# ANET3D_LCD12864_Board.net
KiCad netlist of a schematic drawn in EAGLE
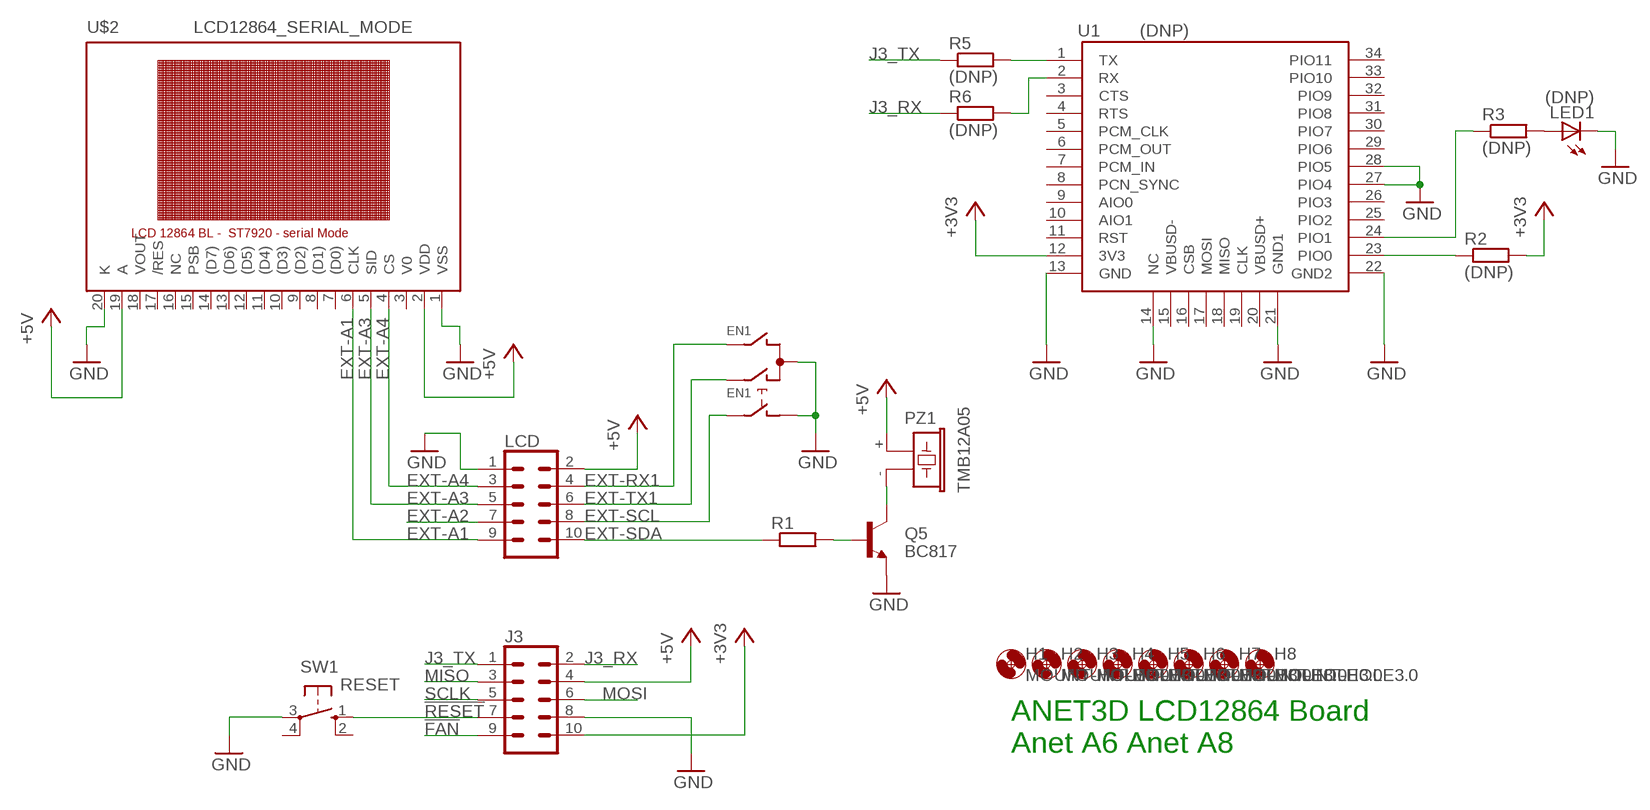
[diagram p0: schematic, sheet 1]

(export (version "E")
  (design (tool "Eeschema 10.0.6"))
  (components
    (comp (ref "EN1")
      (value "EC12E_SW")
      (footprint "eagle-import:ALPS_EC12E_SW")
      (fields (field (name "MPN") "EC12E2424407"))
      (libsource (lib "eagle-import") (part "EC12E_SW"))
    )
    (comp (ref "H1")
      (value "MOUNT-HOLE3.0")
      (footprint "eagle-import:3,0")
      (libsource (lib "eagle-import") (part "MOUNT-HOLE3.0"))
    )
    (comp (ref "H2")
      (value "MOUNT-HOLE3.0")
      (footprint "eagle-import:3,0")
      (libsource (lib "eagle-import") (part "MOUNT-HOLE3.0"))
    )
    (comp (ref "H3")
      (value "MOUNT-HOLE3.0")
      (footprint "eagle-import:3,0")
      (libsource (lib "eagle-import") (part "MOUNT-HOLE3.0"))
    )
    (comp (ref "H4")
      (value "MOUNT-HOLE3.0")
      (footprint "eagle-import:3,0")
      (libsource (lib "eagle-import") (part "MOUNT-HOLE3.0"))
    )
    (comp (ref "H5")
      (value "MOUNT-HOLE3.0")
      (footprint "eagle-import:3,0")
      (libsource (lib "eagle-import") (part "MOUNT-HOLE3.0"))
    )
    (comp (ref "H6")
      (value "MOUNT-HOLE3.0")
      (footprint "eagle-import:3,0")
      (libsource (lib "eagle-import") (part "MOUNT-HOLE3.0"))
    )
    (comp (ref "H7")
      (value "MOUNT-HOLE3.0")
      (footprint "eagle-import:3,0")
      (libsource (lib "eagle-import") (part "MOUNT-HOLE3.0"))
    )
    (comp (ref "H8")
      (value "MOUNT-HOLE3.0")
      (footprint "eagle-import:3,0")
      (libsource (lib "eagle-import") (part "MOUNT-HOLE3.0"))
    )
    (comp (ref "J3")
      (value "CONN_05X2SHD_SMD")
      (footprint "eagle-import:2X5-SHROUDED_SMD")
      (libsource (lib "eagle-import") (part "CONN_05X2SHD_SMD"))
    )
    (comp (ref "LCD")
      (value "CONN_05X2SHD_SMD")
      (footprint "eagle-import:2X5-SHROUDED_SMD")
      (libsource (lib "eagle-import") (part "CONN_05X2SHD_SMD"))
    )
    (comp (ref "LED1")
      (value "(DNP)")
      (footprint "eagle-import:CHIPLED_0805")
      (libsource (lib "eagle-import") (part "LEDCHIPLED_0805"))
    )
    (comp (ref "PZ1")
      (value "TMB12A05")
      (footprint "eagle-import:F_CM12P")
      (libsource (lib "eagle-import") (part "F/CM12P"))
    )
    (comp (ref "Q5")
      (value "BC817")
      (footprint "eagle-import:SOT23-BEC")
      (libsource (lib "eagle-import") (part "BC817SMD-40LT1"))
    )
    (comp (ref "R1")
      (value "R-EU_R0805")
      (footprint "eagle-import:R0805")
      (libsource (lib "eagle-import") (part "R-EU_R0805"))
    )
    (comp (ref "R2")
      (value "(DNP)")
      (footprint "eagle-import:R0805")
      (libsource (lib "eagle-import") (part "R-EU_R0805"))
    )
    (comp (ref "R3")
      (value "(DNP)")
      (footprint "eagle-import:R0805")
      (libsource (lib "eagle-import") (part "R-EU_R0805"))
    )
    (comp (ref "R5")
      (value "(DNP)")
      (footprint "eagle-import:R0805")
      (libsource (lib "eagle-import") (part "R-EU_R0805"))
    )
    (comp (ref "R6")
      (value "(DNP)")
      (footprint "eagle-import:R0805")
      (libsource (lib "eagle-import") (part "R-EU_R0805"))
    )
    (comp (ref "SW1")
      (value "RESET")
      (footprint "eagle-import:B3F-40XX")
      (fields (field (name "MF") "OMRON COMPONENTS USA") (field (name "MPN") "B3F-4000"))
      (libsource (lib "eagle-import") (part "40-XX"))
    )
    (comp (ref "U$2")
      (value "LCD12864_SERIAL_MODE")
      (footprint "eagle-import:LCD12864")
      (libsource (lib "eagle-import") (part "LCD12864_SERIAL_MODE"))
    )
    (comp (ref "U1")
      (value "(DNP)")
      (footprint "eagle-import:BLUETOOTH_SMD")
      (libsource (lib "eagle-import") (part "HC_05"))
    )
  )
  (nets
    (net (code "1") (name "+3V3") (class "Default")
      (node (ref "J3") (pin "10") (pinfunction "10_10") (pintype "passive"))
      (node (ref "R2") (pin "2") (pinfunction "2_2") (pintype "passive"))
      (node (ref "U1") (pin "12") (pinfunction "3V3_12") (pintype "bidirectional"))
    )
    (net (code "2") (name "+5V") (class "Default")
      (node (ref "J3") (pin "4") (pinfunction "4_4") (pintype "passive"))
      (node (ref "LCD") (pin "2") (pinfunction "2_2") (pintype "passive"))
      (node (ref "PZ1") (pin "+") (pinfunction "1_+") (pintype "passive"))
      (node (ref "U$2") (pin "19") (pinfunction "A_19") (pintype "passive"))
      (node (ref "U$2") (pin "2") (pinfunction "VDD_2") (pintype "power_in"))
    )
    (net (code "3") (name "/EXT-A1") (class "Default")
      (node (ref "LCD") (pin "9") (pinfunction "9_9") (pintype "passive"))
      (node (ref "U$2") (pin "6") (pinfunction "CLK_6") (pintype "input"))
    )
    (net (code "4") (name "/EXT-A2") (class "Default")
      (node (ref "LCD") (pin "7") (pinfunction "7_7") (pintype "passive"))
    )
    (net (code "5") (name "/EXT-A3") (class "Default")
      (node (ref "LCD") (pin "5") (pinfunction "5_5") (pintype "passive"))
      (node (ref "U$2") (pin "5") (pinfunction "SID_5") (pintype "input"))
    )
    (net (code "6") (name "/EXT-A4") (class "Default")
      (node (ref "LCD") (pin "3") (pinfunction "3_3") (pintype "passive"))
      (node (ref "U$2") (pin "4") (pinfunction "CS_4") (pintype "input"))
    )
    (net (code "7") (name "/EXT-RX1") (class "Default")
      (node (ref "EN1") (pin "B") (pinfunction "B_B") (pintype "passive"))
      (node (ref "LCD") (pin "4") (pinfunction "4_4") (pintype "passive"))
    )
    (net (code "8") (name "/EXT-SCL") (class "Default")
      (node (ref "EN1") (pin "E") (pinfunction "2_E") (pintype "passive"))
      (node (ref "LCD") (pin "8") (pinfunction "8_8") (pintype "passive"))
    )
    (net (code "9") (name "/EXT-SDA") (class "Default")
      (node (ref "LCD") (pin "10") (pinfunction "10_10") (pintype "passive"))
      (node (ref "R1") (pin "1") (pinfunction "1_1") (pintype "passive"))
    )
    (net (code "10") (name "/EXT-TX1") (class "Default")
      (node (ref "EN1") (pin "A") (pinfunction "A_A") (pintype "passive"))
      (node (ref "LCD") (pin "6") (pinfunction "6_6") (pintype "passive"))
    )
    (net (code "11") (name "/J3_RX") (class "Default")
      (node (ref "J3") (pin "2") (pinfunction "2_2") (pintype "passive"))
      (node (ref "R6") (pin "1") (pinfunction "1_1") (pintype "passive"))
    )
    (net (code "12") (name "/J3_TX") (class "Default")
      (node (ref "J3") (pin "1") (pinfunction "1_1") (pintype "passive"))
      (node (ref "R5") (pin "1") (pinfunction "1_1") (pintype "passive"))
    )
    (net (code "13") (name "/MISO") (class "Default")
      (node (ref "J3") (pin "3") (pinfunction "3_3") (pintype "passive"))
    )
    (net (code "14") (name "/MOSI") (class "Default")
      (node (ref "J3") (pin "6") (pinfunction "6_6") (pintype "passive"))
    )
    (net (code "15") (name "/SCLK") (class "Default")
      (node (ref "J3") (pin "5") (pinfunction "5_5") (pintype "passive"))
    )
    (net (code "16") (name "/~{FAN}") (class "Default")
      (node (ref "J3") (pin "9") (pinfunction "9_9") (pintype "passive"))
    )
    (net (code "17") (name "/~{RESET}") (class "Default")
      (node (ref "J3") (pin "7") (pinfunction "7_7") (pintype "passive"))
      (node (ref "SW1") (pin "1") (pinfunction "S_1") (pintype "passive"))
    )
    (net (code "18") (name "GND") (class "Default")
      (node (ref "EN1") (pin "C") (pinfunction "C_C") (pintype "passive"))
      (node (ref "EN1") (pin "D") (pinfunction "1_D") (pintype "passive"))
      (node (ref "J3") (pin "8") (pinfunction "8_8") (pintype "passive"))
      (node (ref "LCD") (pin "1") (pinfunction "1_1") (pintype "passive"))
      (node (ref "LED1") (pin "C") (pinfunction "C_C") (pintype "passive"))
      (node (ref "Q5") (pin "E") (pinfunction "E_E") (pintype "passive"))
      (node (ref "SW1") (pin "3") (pinfunction "P_3") (pintype "passive"))
      (node (ref "U$2") (pin "1") (pinfunction "VSS_1") (pintype "power_in"))
      (node (ref "U$2") (pin "20") (pinfunction "K_20") (pintype "passive"))
      (node (ref "U1") (pin "13") (pinfunction "GND_13") (pintype "bidirectional"))
      (node (ref "U1") (pin "14") (pinfunction "NC_14") (pintype "bidirectional"))
      (node (ref "U1") (pin "21") (pinfunction "GND1_21") (pintype "bidirectional"))
      (node (ref "U1") (pin "22") (pinfunction "GND2_22") (pintype "bidirectional"))
      (node (ref "U1") (pin "27") (pinfunction "PIO4_27") (pintype "bidirectional"))
      (node (ref "U1") (pin "28") (pinfunction "PIO5_28") (pintype "bidirectional"))
    )
    (net (code "19") (name "Net-(LED1-PadA)") (class "Default")
      (node (ref "LED1") (pin "A") (pinfunction "A_A") (pintype "passive"))
      (node (ref "R3") (pin "2") (pinfunction "2_2") (pintype "passive"))
    )
    (net (code "20") (name "Net-(PZ1-2)") (class "Default")
      (node (ref "PZ1") (pin "-") (pinfunction "2_-") (pintype "passive"))
      (node (ref "Q5") (pin "C") (pinfunction "C_C") (pintype "passive"))
    )
    (net (code "21") (name "Net-(Q5-PadB)") (class "Default")
      (node (ref "Q5") (pin "B") (pinfunction "B_B") (pintype "passive"))
      (node (ref "R1") (pin "2") (pinfunction "2_2") (pintype "passive"))
    )
    (net (code "22") (name "Net-(U1-PIO0)") (class "Default")
      (node (ref "R2") (pin "1") (pinfunction "1_1") (pintype "passive"))
      (node (ref "U1") (pin "23") (pinfunction "PIO0_23") (pintype "bidirectional"))
    )
    (net (code "23") (name "Net-(U1-PIO1)") (class "Default")
      (node (ref "R3") (pin "1") (pinfunction "1_1") (pintype "passive"))
      (node (ref "U1") (pin "24") (pinfunction "PIO1_24") (pintype "bidirectional"))
    )
    (net (code "24") (name "Net-(U1-RX)") (class "Default")
      (node (ref "R6") (pin "2") (pinfunction "2_2") (pintype "passive"))
      (node (ref "U1") (pin "2") (pinfunction "RX_2") (pintype "bidirectional"))
    )
    (net (code "25") (name "Net-(U1-TX)") (class "Default")
      (node (ref "R5") (pin "2") (pinfunction "2_2") (pintype "passive"))
      (node (ref "U1") (pin "1") (pinfunction "TX_1") (pintype "bidirectional"))
    )
    (net (code "26") (name "unconnected-(SW1-P1-Pad4)") (class "Default")
      (node (ref "SW1") (pin "4") (pinfunction "P1_4") (pintype "passive"))
    )
    (net (code "27") (name "unconnected-(SW1-S1-Pad2)") (class "Default")
      (node (ref "SW1") (pin "2") (pinfunction "S1_2") (pintype "passive"))
    )
    (net (code "28") (name "unconnected-(U$2-(D0)-Pad7)") (class "Default")
      (node (ref "U$2") (pin "7") (pinfunction "(D0)_7") (pintype "bidirectional"))
    )
    (net (code "29") (name "unconnected-(U$2-(D1)-Pad8)") (class "Default")
      (node (ref "U$2") (pin "8") (pinfunction "(D1)_8") (pintype "bidirectional"))
    )
    (net (code "30") (name "unconnected-(U$2-(D2)-Pad9)") (class "Default")
      (node (ref "U$2") (pin "9") (pinfunction "(D2)_9") (pintype "bidirectional"))
    )
    (net (code "31") (name "unconnected-(U$2-(D3)-Pad10)") (class "Default")
      (node (ref "U$2") (pin "10") (pinfunction "(D3)_10") (pintype "bidirectional"))
    )
    (net (code "32") (name "unconnected-(U$2-(D4)-Pad11)") (class "Default")
      (node (ref "U$2") (pin "11") (pinfunction "(D4)_11") (pintype "bidirectional"))
    )
    (net (code "33") (name "unconnected-(U$2-(D5)-Pad12)") (class "Default")
      (node (ref "U$2") (pin "12") (pinfunction "(D5)_12") (pintype "bidirectional"))
    )
    (net (code "34") (name "unconnected-(U$2-(D6)-Pad13)") (class "Default")
      (node (ref "U$2") (pin "13") (pinfunction "(D6)_13") (pintype "bidirectional"))
    )
    (net (code "35") (name "unconnected-(U$2-(D7)-Pad14)") (class "Default")
      (node (ref "U$2") (pin "14") (pinfunction "(D7)_14") (pintype "bidirectional"))
    )
    (net (code "36") (name "unconnected-(U$2-NC-Pad16)") (class "Default")
      (node (ref "U$2") (pin "16") (pinfunction "NC_16") (pintype "input"))
    )
    (net (code "37") (name "unconnected-(U$2-PSB-Pad15)") (class "Default")
      (node (ref "U$2") (pin "15") (pinfunction "PSB_15") (pintype "input"))
    )
    (net (code "38") (name "unconnected-(U$2-V0-Pad3)") (class "Default")
      (node (ref "U$2") (pin "3") (pinfunction "V0_3") (pintype "passive"))
    )
    (net (code "39") (name "unconnected-(U$2-VOUT-Pad18)") (class "Default")
      (node (ref "U$2") (pin "18") (pinfunction "VOUT_18") (pintype "output"))
    )
    (net (code "40") (name "unconnected-(U$2-{slash}RES-Pad17)") (class "Default")
      (node (ref "U$2") (pin "17") (pinfunction "/RES_17") (pintype "input"))
    )
    (net (code "41") (name "unconnected-(U1-AIO0-Pad9)") (class "Default")
      (node (ref "U1") (pin "9") (pinfunction "AIO0_9") (pintype "bidirectional"))
    )
    (net (code "42") (name "unconnected-(U1-AIO1-Pad10)") (class "Default")
      (node (ref "U1") (pin "10") (pinfunction "AIO1_10") (pintype "bidirectional"))
    )
    (net (code "43") (name "unconnected-(U1-CLK-Pad19)") (class "Default")
      (node (ref "U1") (pin "19") (pinfunction "CLK_19") (pintype "bidirectional"))
    )
    (net (code "44") (name "unconnected-(U1-CSB-Pad16)") (class "Default")
      (node (ref "U1") (pin "16") (pinfunction "CSB_16") (pintype "bidirectional"))
    )
    (net (code "45") (name "unconnected-(U1-CTS-Pad3)") (class "Default")
      (node (ref "U1") (pin "3") (pinfunction "CTS_3") (pintype "bidirectional"))
    )
    (net (code "46") (name "unconnected-(U1-MISO-Pad18)") (class "Default")
      (node (ref "U1") (pin "18") (pinfunction "MISO_18") (pintype "bidirectional"))
    )
    (net (code "47") (name "unconnected-(U1-MOSI-Pad17)") (class "Default")
      (node (ref "U1") (pin "17") (pinfunction "MOSI_17") (pintype "bidirectional"))
    )
    (net (code "48") (name "unconnected-(U1-PCM_CLK-Pad5)") (class "Default")
      (node (ref "U1") (pin "5") (pinfunction "PCM_CLK_5") (pintype "bidirectional"))
    )
    (net (code "49") (name "unconnected-(U1-PCM_IN-Pad7)") (class "Default")
      (node (ref "U1") (pin "7") (pinfunction "PCM_IN_7") (pintype "bidirectional"))
    )
    (net (code "50") (name "unconnected-(U1-PCM_OUT-Pad6)") (class "Default")
      (node (ref "U1") (pin "6") (pinfunction "PCM_OUT_6") (pintype "bidirectional"))
    )
    (net (code "51") (name "unconnected-(U1-PCN_SYNC-Pad8)") (class "Default")
      (node (ref "U1") (pin "8") (pinfunction "PCN_SYNC_8") (pintype "bidirectional"))
    )
    (net (code "52") (name "unconnected-(U1-PIO2-Pad25)") (class "Default")
      (node (ref "U1") (pin "25") (pinfunction "PIO2_25") (pintype "bidirectional"))
    )
    (net (code "53") (name "unconnected-(U1-PIO3-Pad26)") (class "Default")
      (node (ref "U1") (pin "26") (pinfunction "PIO3_26") (pintype "bidirectional"))
    )
    (net (code "54") (name "unconnected-(U1-PIO6-Pad29)") (class "Default")
      (node (ref "U1") (pin "29") (pinfunction "PIO6_29") (pintype "bidirectional"))
    )
    (net (code "55") (name "unconnected-(U1-PIO7-Pad30)") (class "Default")
      (node (ref "U1") (pin "30") (pinfunction "PIO7_30") (pintype "bidirectional"))
    )
    (net (code "56") (name "unconnected-(U1-PIO8-Pad31)") (class "Default")
      (node (ref "U1") (pin "31") (pinfunction "PIO8_31") (pintype "bidirectional"))
    )
    (net (code "57") (name "unconnected-(U1-PIO9-Pad32)") (class "Default")
      (node (ref "U1") (pin "32") (pinfunction "PIO9_32") (pintype "bidirectional"))
    )
    (net (code "58") (name "unconnected-(U1-PIO10-Pad33)") (class "Default")
      (node (ref "U1") (pin "33") (pinfunction "PIO10_33") (pintype "bidirectional"))
    )
    (net (code "59") (name "unconnected-(U1-PIO11-Pad34)") (class "Default")
      (node (ref "U1") (pin "34") (pinfunction "PIO11_34") (pintype "bidirectional"))
    )
    (net (code "60") (name "unconnected-(U1-RST-Pad11)") (class "Default")
      (node (ref "U1") (pin "11") (pinfunction "RST_11") (pintype "bidirectional"))
    )
    (net (code "61") (name "unconnected-(U1-RTS-Pad4)") (class "Default")
      (node (ref "U1") (pin "4") (pinfunction "RTS_4") (pintype "bidirectional"))
    )
    (net (code "62") (name "unconnected-(U1-VBUSD+-Pad20)") (class "Default")
      (node (ref "U1") (pin "20") (pinfunction "VBUSD+_20") (pintype "bidirectional"))
    )
    (net (code "63") (name "unconnected-(U1-VBUSD--Pad15)") (class "Default")
      (node (ref "U1") (pin "15") (pinfunction "VBUSD-_15") (pintype "bidirectional"))
    )
  )
)
